# sensor_circuit.net
KiCad netlist of a schematic drawn in EAGLE
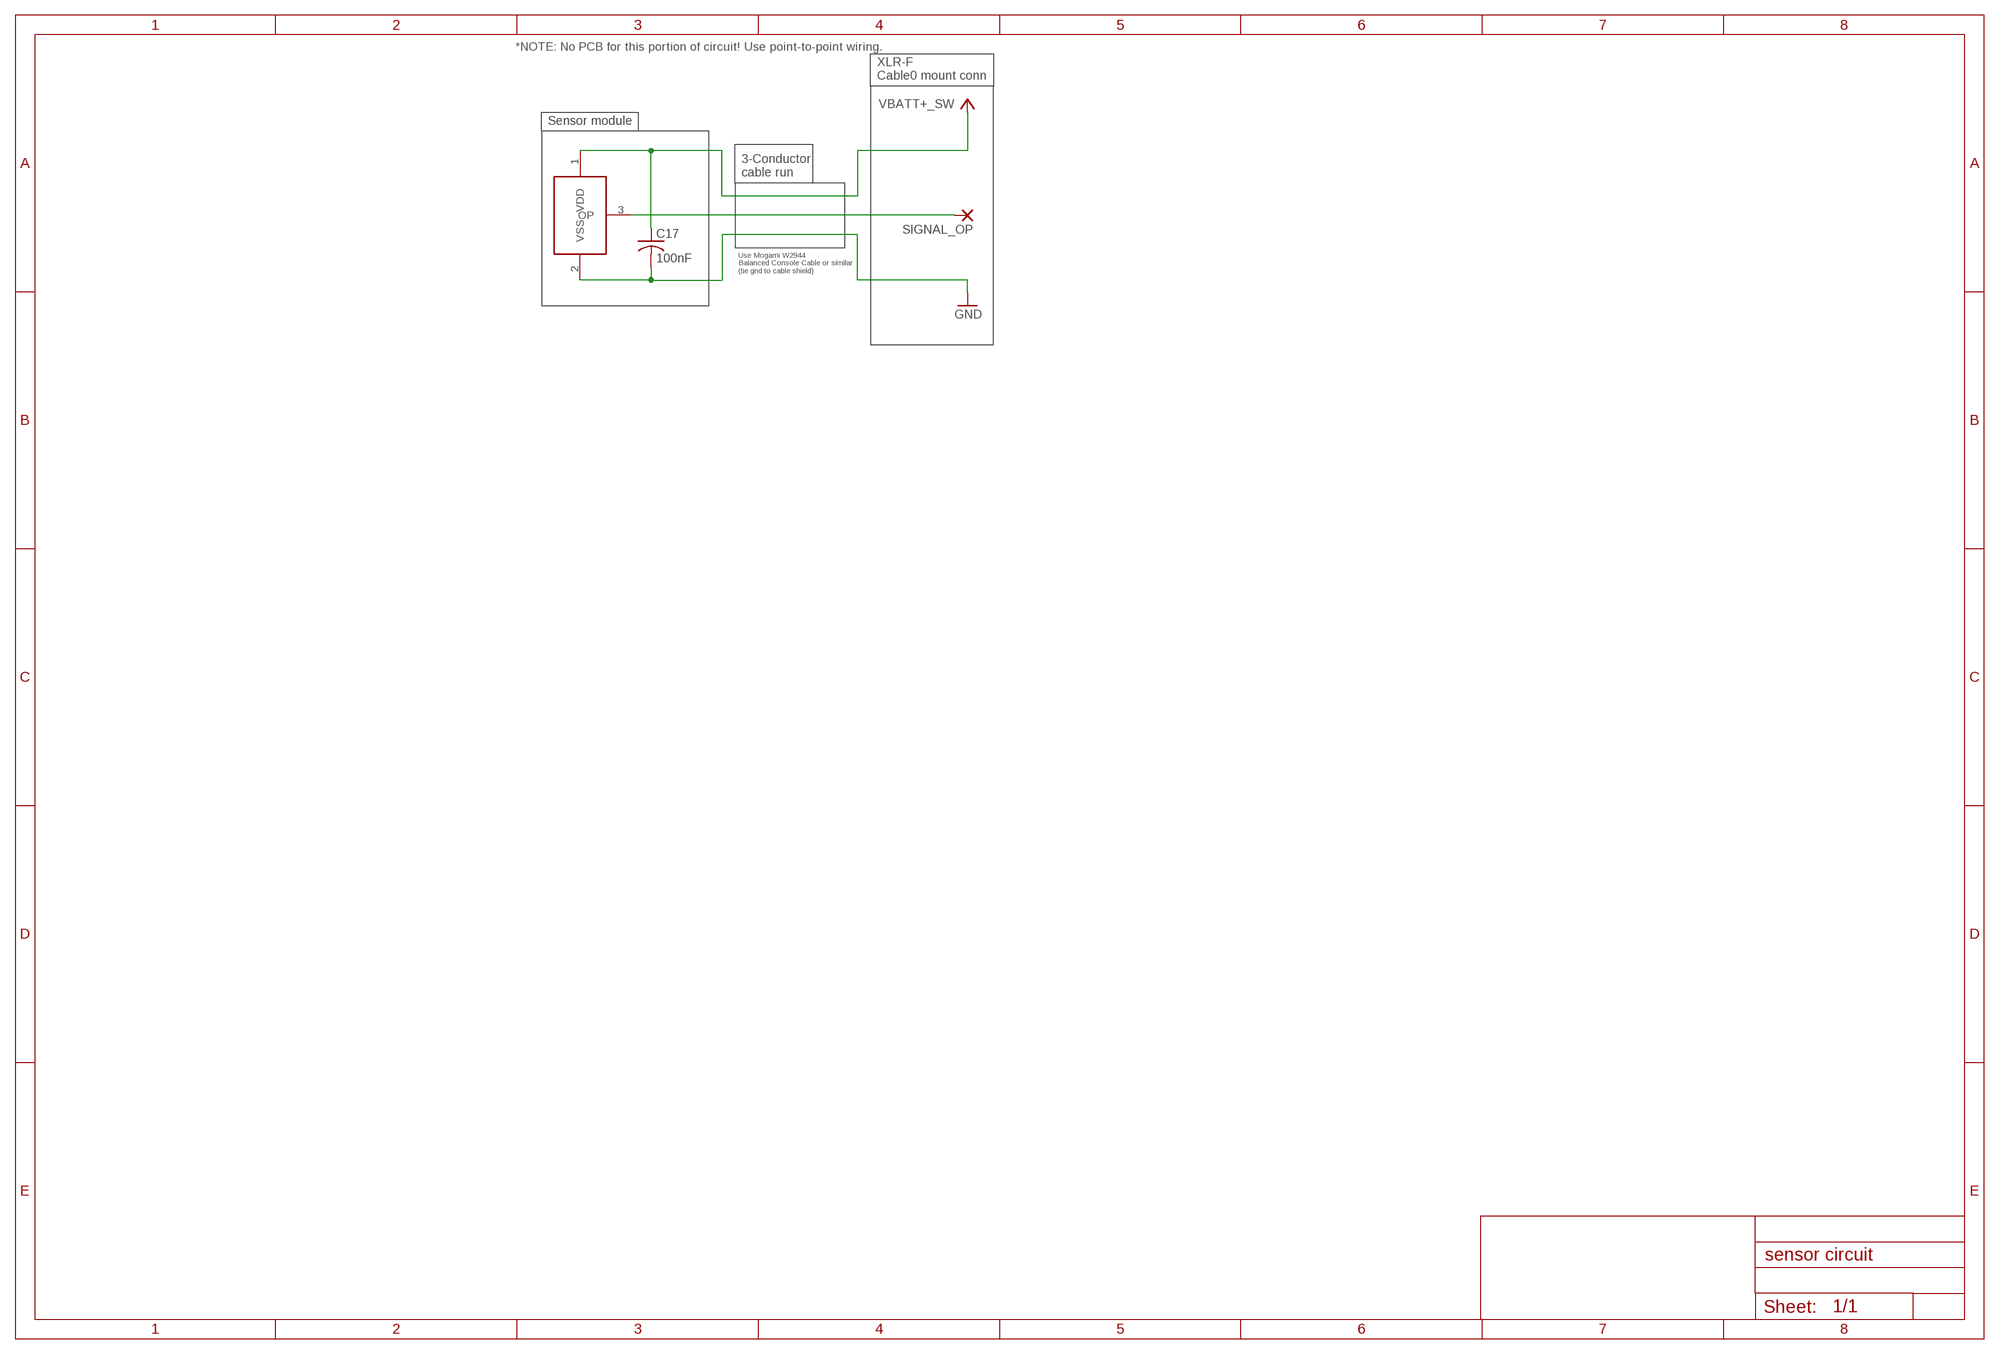
[diagram p0: schematic, sheet 1]

(export (version "E")
  (design (tool "Eeschema 10.0.6"))
  (components
    (comp (ref "C17")
      (value "100nF")
      (footprint "eagle-import:C025-024X044")
      (libsource (lib "eagle-import") (part "C-US025-024X044"))
    )
    (comp (ref "SIGNAL_OP")
      (value "1,6/0,8")
      (footprint "eagle-import:1,6_0,8")
      (libsource (lib "eagle-import") (part "1,6/0,8"))
    )
    (comp (ref "U1A")
      (value "US5881")
      (footprint "eagle-import:TO-92")
      (libsource (lib "eagle-import") (part "US5881"))
    )
  )
  (nets
    (net (code "1") (name "GND") (class "Default")
      (node (ref "C17") (pin "2") (pinfunction "2_2") (pintype "passive"))
      (node (ref "U1A") (pin "2") (pinfunction "VSS_2") (pintype "bidirectional"))
    )
    (net (code "2") (name "Net-(SIGNAL_OP-P)") (class "Default")
      (node (ref "SIGNAL_OP") (pin "1") (pinfunction "P_1") (pintype "passive"))
      (node (ref "U1A") (pin "3") (pinfunction "OP_3") (pintype "bidirectional"))
    )
    (net (code "3") (name "VBATT+_SW") (class "Default")
      (node (ref "C17") (pin "1") (pinfunction "1_1") (pintype "passive"))
      (node (ref "U1A") (pin "1") (pinfunction "VDD_1") (pintype "bidirectional"))
    )
  )
)
